# input_power_switching.net
KiCad netlist of a schematic drawn in Altium Designer
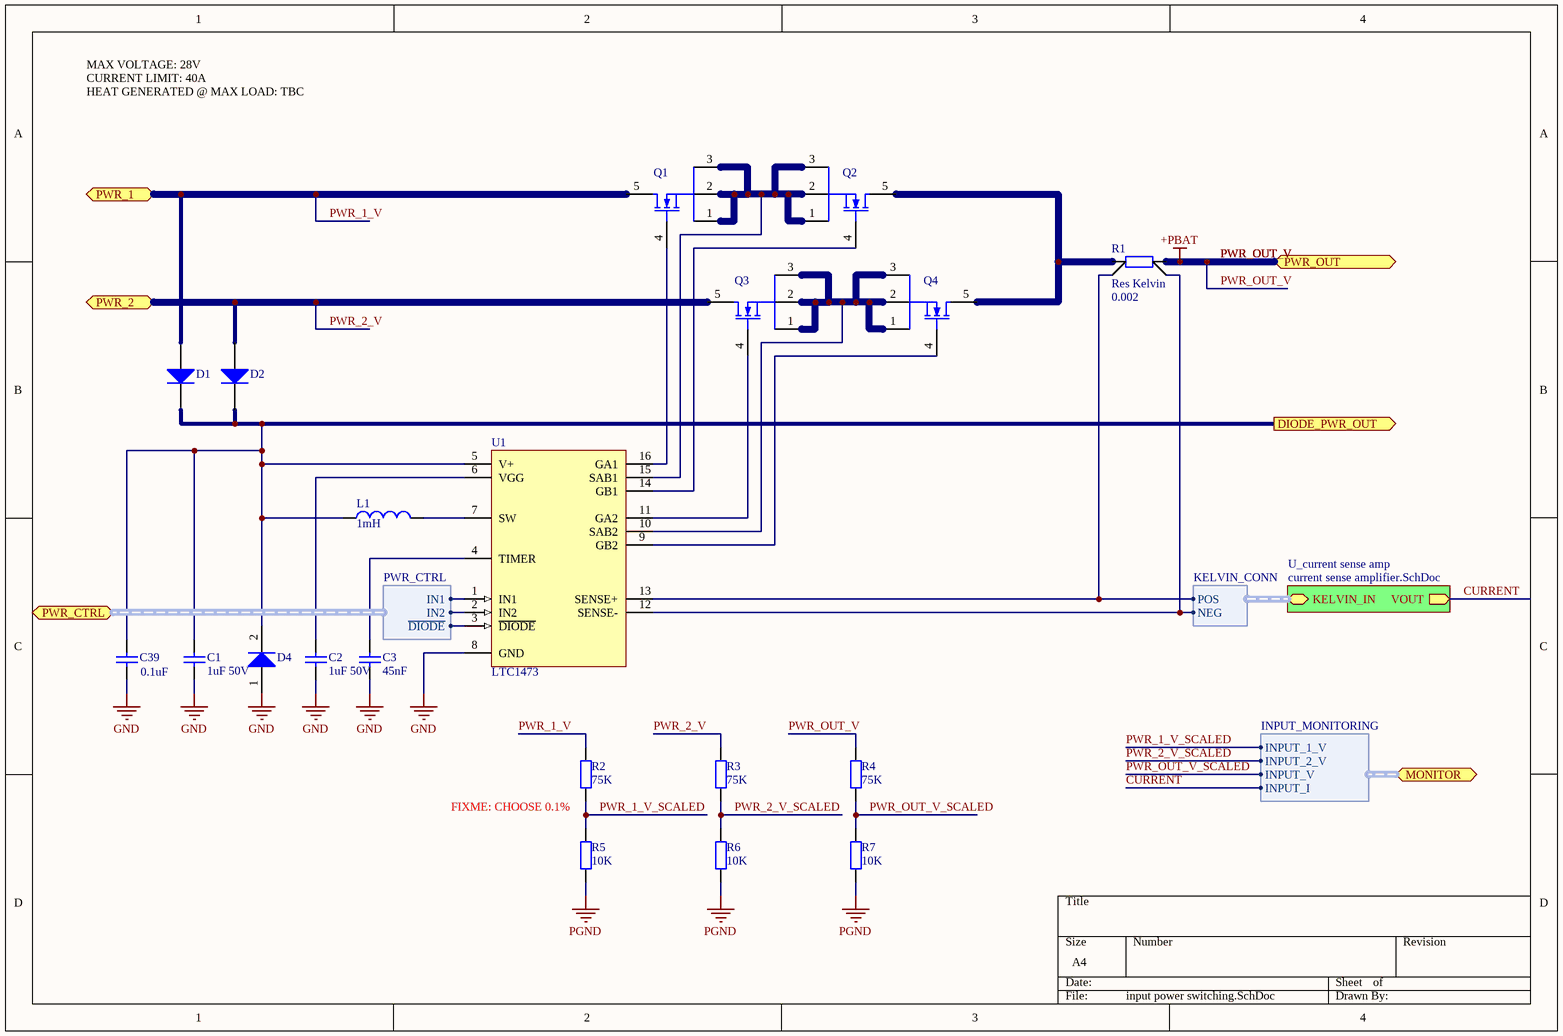
[diagram p0: input power switching.SchDoc]

(export (version "E")
  (design (tool "Eeschema 10.0.6"))
  (components
    (comp (ref "C1")
      (value "1uF 50V")
      (footprint "C0603")
      (description "Capacitor")
      (fields (field (name "Comment") "Cap") (field (name "PUBLISHER") "Altium Limited"))
      (libsource (lib "Miscellaneous Devices") (part "Cap"))
    )
    (comp (ref "C2")
      (value "1uF 50V")
      (footprint "C0603")
      (description "Capacitor")
      (fields (field (name "Comment") "Cap") (field (name "PUBLISHER") "Altium Limited"))
      (libsource (lib "Miscellaneous Devices") (part "Cap"))
    )
    (comp (ref "C3")
      (value "45nF")
      (footprint "C0603")
      (description "Capacitor")
      (fields (field (name "Comment") "Cap") (field (name "PUBLISHER") "Altium Limited"))
      (libsource (lib "Miscellaneous Devices") (part "Cap"))
    )
    (comp (ref "C39")
      (value "0.1uF")
      (footprint "C0603")
      (description "Capacitor")
      (fields (field (name "Comment") "Cap") (field (name "PUBLISHER") "Altium Limited"))
      (libsource (lib "Miscellaneous Devices") (part "Cap"))
    )
    (comp (ref "D1")
      (value "Diode")
      (footprint "VS-10BQ030TRPBF")
      (description "Default Diode")
      (fields (field (name "PUBLISHER") "Altium Limited"))
      (libsource (lib "Miscellaneous Devices") (part "Diode"))
    )
    (comp (ref "D2")
      (value "Diode")
      (footprint "VS-10BQ030TRPBF")
      (description "Default Diode")
      (fields (field (name "PUBLISHER") "Altium Limited"))
      (libsource (lib "Miscellaneous Devices") (part "Diode"))
    )
    (comp (ref "D4")
      (value "Diode")
      (footprint "MMBD914LT1G")
      (description "Default Diode")
      (fields (field (name "PUBLISHER") "Altium Limited"))
      (libsource (lib "") (part "Diode_1"))
    )
    (comp (ref "L1")
      (value "1mH")
      (footprint "744045102")
      (description "Inductor")
      (fields (field (name "PUBLISHER") "Altium Limited"))
      (libsource (lib "Miscellaneous Devices") (part "Inductor"))
    )
    (comp (ref "Q1")
      (value "PSMN1R7-30YL")
      (footprint "PSMN1R7-30YL")
      (description "NXP - PSMN1R7-30YL - MOSFET, N CH 30V 100A SOT669")
      (libsource (lib "PSMN1R7-30YL") (part "PSMN1R7-30YL"))
    )
    (comp (ref "Q2")
      (value "PSMN1R7-30YL")
      (footprint "PSMN1R7-30YL")
      (description "NXP - PSMN1R7-30YL - MOSFET, N CH 30V 100A SOT669")
      (libsource (lib "PSMN1R7-30YL") (part "PSMN1R7-30YL"))
    )
    (comp (ref "Q3")
      (value "PSMN1R7-30YL")
      (footprint "PSMN1R7-30YL")
      (description "NXP - PSMN1R7-30YL - MOSFET, N CH 30V 100A SOT669")
      (libsource (lib "PSMN1R7-30YL") (part "PSMN1R7-30YL"))
    )
    (comp (ref "Q4")
      (value "PSMN1R7-30YL")
      (footprint "PSMN1R7-30YL")
      (description "NXP - PSMN1R7-30YL - MOSFET, N CH 30V 100A SOT669")
      (libsource (lib "PSMN1R7-30YL") (part "PSMN1R7-30YL"))
    )
    (comp (ref "R1")
      (value "Res Kelvin")
      (footprint "WSR32L000FEA")
      (description "Resistor Kelvin")
      (fields (field (name "ALTIUM_VALUE") "0.002") (field (name "PUBLISHER") "Altium Limited"))
      (libsource (lib "resistor-kelvin") (part "Res Kelvin"))
    )
    (comp (ref "R2")
      (value "75K")
      (footprint "R0603")
      (description "Resistor")
      (fields (field (name "Comment") "Res2") (field (name "PUBLISHER") "Altium Limited"))
      (libsource (lib "") (part "Res2_1"))
    )
    (comp (ref "R3")
      (value "75K")
      (footprint "R0603")
      (description "Resistor")
      (fields (field (name "Comment") "Res2") (field (name "PUBLISHER") "Altium Limited"))
      (libsource (lib "") (part "Res2_1"))
    )
    (comp (ref "R4")
      (value "75K")
      (footprint "R0603")
      (description "Resistor")
      (fields (field (name "Comment") "Res2") (field (name "PUBLISHER") "Altium Limited"))
      (libsource (lib "Miscellaneous Devices") (part "Res2"))
    )
    (comp (ref "R5")
      (value "10K")
      (footprint "R0603")
      (description "Resistor")
      (fields (field (name "Comment") "Res"))
      (libsource (lib "") (part "Res2_2"))
    )
    (comp (ref "R6")
      (value "10K")
      (footprint "R0603")
      (description "Resistor")
      (fields (field (name "Comment") "Res"))
      (libsource (lib "") (part "Res2_2"))
    )
    (comp (ref "R7")
      (value "10K")
      (footprint "R0603")
      (description "Resistor")
      (fields (field (name "Comment") "Res"))
      (libsource (lib "") (part "Res2_2"))
    )
    (comp (ref "U1")
      (value "LTC1473")
      (footprint "LTC1473")
      (description "IC SWITCH DVR PWRPATH DUAL16SSOP")
      (libsource (lib "LTC1473") (part "LTC1473"))
    )
  )
  (nets
    (net (code "4") (name "+PBAT") (class "Default")
      (node (ref "R4") (pin "1") (pinfunction "1_1") (pintype "passive"))
    )
    (net (code "6") (name "/DIODE_PWR_OUT") (class "Default")
      (node (ref "C1") (pin "2") (pinfunction "2_2") (pintype "passive"))
      (node (ref "C39") (pin "2") (pinfunction "2_2") (pintype "passive"))
      (node (ref "D1") (pin "2") (pinfunction "K_2") (pintype "passive"))
      (node (ref "D2") (pin "2") (pinfunction "K_2") (pintype "passive"))
      (node (ref "D4") (pin "2") (pinfunction "K_2") (pintype "passive"))
      (node (ref "L1") (pin "1") (pinfunction "1_1") (pintype "passive"))
      (node (ref "U1") (pin "5") (pinfunction "V+_5") (pintype "power_in"))
    )
    (net (code "7") (name "/IN1") (class "Default")
      (node (ref "U1") (pin "1") (pinfunction "IN1_1") (pintype "input"))
    )
    (net (code "8") (name "/IN2") (class "Default")
      (node (ref "U1") (pin "2") (pinfunction "IN2_2") (pintype "input"))
    )
    (net (code "9") (name "/NEG") (class "Default")
      (node (ref "R1") (pin "3") (pinfunction "3_3") (pintype "power_in"))
      (node (ref "U1") (pin "12") (pinfunction "SENSE-_12") (pintype "passive"))
    )
    (net (code "10") (name "/POS") (class "Default")
      (node (ref "R1") (pin "4") (pinfunction "4_4") (pintype "power_in"))
      (node (ref "U1") (pin "13") (pinfunction "SENSE+_13") (pintype "passive"))
    )
    (net (code "11") (name "/PWR_1_V") (class "Default")
      (node (ref "D1") (pin "1") (pinfunction "A_1") (pintype "passive"))
      (node (ref "Q1") (pin "5") (pinfunction "D_5") (pintype "passive"))
      (node (ref "R2") (pin "2") (pinfunction "2_2") (pintype "passive"))
    )
    (net (code "12") (name "/PWR_1_V_SCALED") (class "Default")
      (node (ref "R2") (pin "1") (pinfunction "1_1") (pintype "passive"))
      (node (ref "R5") (pin "1") (pinfunction "1_1") (pintype "passive"))
    )
    (net (code "13") (name "/PWR_2_V") (class "Default")
      (node (ref "D2") (pin "1") (pinfunction "A_1") (pintype "passive"))
      (node (ref "Q3") (pin "5") (pinfunction "D_5") (pintype "passive"))
      (node (ref "R3") (pin "2") (pinfunction "2_2") (pintype "passive"))
    )
    (net (code "14") (name "/PWR_2_V_SCALED") (class "Default")
      (node (ref "R3") (pin "1") (pinfunction "1_1") (pintype "passive"))
      (node (ref "R6") (pin "1") (pinfunction "1_1") (pintype "passive"))
    )
    (net (code "15") (name "/PWR_OUT_V_SCALED") (class "Default")
      (node (ref "R4") (pin "1") (pinfunction "1_1") (pintype "passive"))
      (node (ref "R7") (pin "1") (pinfunction "1_1") (pintype "passive"))
    )
    (net (code "19") (name "/~{DIODE}") (class "Default")
      (node (ref "U1") (pin "3") (pinfunction "~{DIODE}_3") (pintype "input"))
    )
    (net (code "20") (name "GND") (class "Default")
      (node (ref "C1") (pin "1") (pinfunction "1_1") (pintype "passive"))
      (node (ref "C2") (pin "1") (pinfunction "1_1") (pintype "passive"))
      (node (ref "C3") (pin "1") (pinfunction "1_1") (pintype "passive"))
      (node (ref "C39") (pin "1") (pinfunction "1_1") (pintype "passive"))
      (node (ref "D4") (pin "1") (pinfunction "A_1") (pintype "passive"))
      (node (ref "U1") (pin "8") (pinfunction "GND_8") (pintype "power_in"))
    )
    (net (code "21") (name "Net-(Q1-G)") (class "Default")
      (node (ref "Q1") (pin "4") (pinfunction "G_4") (pintype "passive"))
      (node (ref "U1") (pin "16") (pinfunction "GA1_16") (pintype "passive"))
    )
    (net (code "22") (name "Net-(Q2-D)") (class "Default")
      (node (ref "Q2") (pin "5") (pinfunction "D_5") (pintype "passive"))
      (node (ref "Q4") (pin "5") (pinfunction "D_5") (pintype "passive"))
      (node (ref "R1") (pin "2") (pinfunction "2_2") (pintype "passive"))
    )
    (net (code "23") (name "Net-(Q2-G)") (class "Default")
      (node (ref "Q2") (pin "4") (pinfunction "G_4") (pintype "passive"))
      (node (ref "U1") (pin "14") (pinfunction "GB1_14") (pintype "passive"))
    )
    (net (code "24") (name "Net-(Q3-G)") (class "Default")
      (node (ref "Q3") (pin "4") (pinfunction "G_4") (pintype "passive"))
      (node (ref "U1") (pin "11") (pinfunction "GA2_11") (pintype "passive"))
    )
    (net (code "25") (name "Net-(Q4-G)") (class "Default")
      (node (ref "Q4") (pin "4") (pinfunction "G_4") (pintype "passive"))
      (node (ref "U1") (pin "9") (pinfunction "GB2_9") (pintype "passive"))
    )
    (net (code "26") (name "Net-(U1-SAB1)") (class "Default")
      (node (ref "Q1") (pin "1") (pinfunction "S_1") (pintype "passive"))
      (node (ref "Q1") (pin "2") (pinfunction "S_2") (pintype "passive"))
      (node (ref "Q1") (pin "3") (pinfunction "S_3") (pintype "passive"))
      (node (ref "Q2") (pin "1") (pinfunction "S_1") (pintype "passive"))
      (node (ref "Q2") (pin "2") (pinfunction "S_2") (pintype "passive"))
      (node (ref "Q2") (pin "3") (pinfunction "S_3") (pintype "passive"))
      (node (ref "U1") (pin "15") (pinfunction "SAB1_15") (pintype "passive"))
    )
    (net (code "27") (name "Net-(U1-SAB2)") (class "Default")
      (node (ref "Q3") (pin "1") (pinfunction "S_1") (pintype "passive"))
      (node (ref "Q3") (pin "2") (pinfunction "S_2") (pintype "passive"))
      (node (ref "Q3") (pin "3") (pinfunction "S_3") (pintype "passive"))
      (node (ref "Q4") (pin "1") (pinfunction "S_1") (pintype "passive"))
      (node (ref "Q4") (pin "2") (pinfunction "S_2") (pintype "passive"))
      (node (ref "Q4") (pin "3") (pinfunction "S_3") (pintype "passive"))
      (node (ref "U1") (pin "10") (pinfunction "SAB2_10") (pintype "passive"))
    )
    (net (code "28") (name "Net-(U1-SW)") (class "Default")
      (node (ref "L1") (pin "2") (pinfunction "2_2") (pintype "passive"))
      (node (ref "U1") (pin "7") (pinfunction "SW_7") (pintype "passive"))
    )
    (net (code "29") (name "Net-(U1-TIMER)") (class "Default")
      (node (ref "C3") (pin "2") (pinfunction "2_2") (pintype "passive"))
      (node (ref "U1") (pin "4") (pinfunction "TIMER_4") (pintype "passive"))
    )
    (net (code "30") (name "Net-(U1-VGG)") (class "Default")
      (node (ref "C2") (pin "2") (pinfunction "2_2") (pintype "passive"))
      (node (ref "U1") (pin "6") (pinfunction "VGG_6") (pintype "passive"))
    )
    (net (code "31") (name "PGND") (class "Default")
      (node (ref "R5") (pin "2") (pinfunction "2_2") (pintype "passive"))
      (node (ref "R6") (pin "2") (pinfunction "2_2") (pintype "passive"))
      (node (ref "R7") (pin "2") (pinfunction "2_2") (pintype "passive"))
    )
    (net (code "32") (name "unconnected-(R1-Pad1)") (class "Default")
      (node (ref "R1") (pin "1") (pinfunction "1_1") (pintype "passive"))
    )
  )
)
